# PressureCurrentSource.net
KiCad netlist of a schematic drawn in Altium Designer
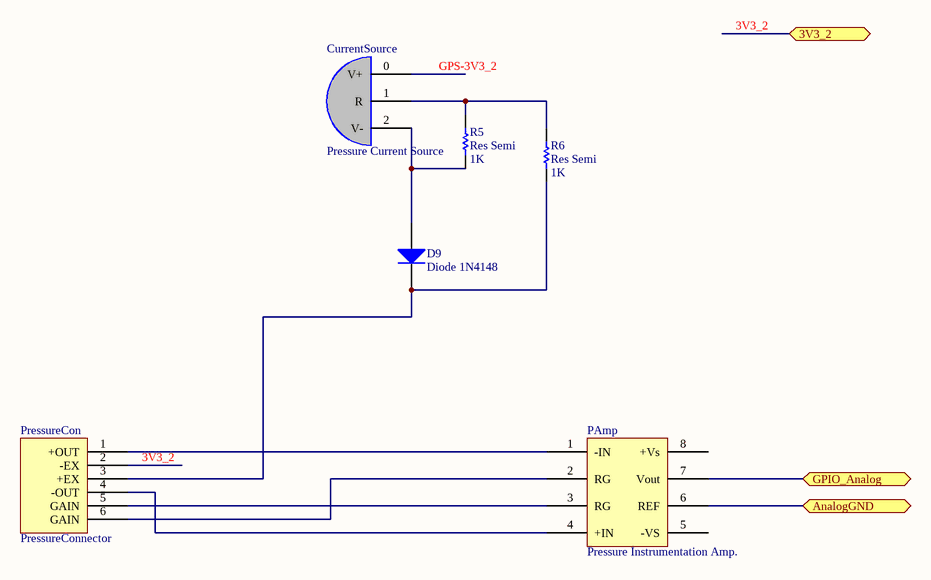
[diagram p0: PressureCurrentSource.SchDoc]

(export (version "E")
  (design (tool "Eeschema 10.0.6"))
  (components
    (comp (ref "CurrentSource")
      (value "Pressure Current Source")
      (footprint "UmbilicalConnectors:Pressure Current Source")
      (libsource (lib "UmbilicalBoardV2") (part "Pressure Current Source"))
    )
    (comp (ref "D9")
      (value "Diode 1N4148")
      (footprint "DO-35")
      (description "High Conductance Fast Diode")
      (fields (field (name "PUBLISHER") "Altium Limited"))
      (libsource (lib "Miscellaneous Devices") (part "Diode 1N4148"))
    )
    (comp (ref "PAmp")
      (value "Pressure Instrumentation Amp.")
      (footprint "UmbilicalConnectors:Pressure Instrumentation Amp.")
      (libsource (lib "UmbilicalBoardV2") (part "Pressure Instrumentation Amp."))
    )
    (comp (ref "PressureCon")
      (value "PressureConnector")
      (footprint "UmbilicalConnectors:Pressure Connector")
      (description "Molex 70553-0005")
      (libsource (lib "UmbilicalBoardV2") (part "PressureConnector"))
    )
    (comp (ref "R5")
      (value "Res Semi")
      (footprint "AXIAL-0.5")
      (description "Semiconductor Resistor")
      (fields (field (name "ALTIUM_VALUE") "1K") (field (name "PUBLISHER") "Altium Limited"))
      (libsource (lib "Miscellaneous Devices") (part "Res Semi"))
    )
    (comp (ref "R6")
      (value "Res Semi")
      (footprint "AXIAL-0.5")
      (description "Semiconductor Resistor")
      (fields (field (name "ALTIUM_VALUE") "1K") (field (name "PUBLISHER") "Altium Limited"))
      (libsource (lib "Miscellaneous Devices") (part "Res Semi"))
    )
  )
  (nets
    (net (code "1") (name "/3V3_2") (class "Default")
      (node (ref "PressureCon") (pin "2") (pinfunction "-EX_2") (pintype "passive"))
    )
    (net (code "2") (name "/AnalogGND") (class "Default")
      (node (ref "PAmp") (pin "6") (pinfunction "REF_6") (pintype "passive"))
    )
    (net (code "3") (name "/GPIO_Analog") (class "Default")
      (node (ref "PAmp") (pin "7") (pinfunction "Vout_7") (pintype "passive"))
    )
    (net (code "4") (name "/GPS-3V3_2") (class "Default")
      (node (ref "CurrentSource") (pin "0") (pinfunction "V+_0") (pintype "passive"))
    )
    (net (code "5") (name "Net-(CurrentSource-R)") (class "Default")
      (node (ref "CurrentSource") (pin "1") (pinfunction "R_1") (pintype "passive"))
      (node (ref "R5") (pin "2") (pinfunction "2_2") (pintype "passive"))
      (node (ref "R6") (pin "2") (pinfunction "2_2") (pintype "passive"))
    )
    (net (code "6") (name "Net-(CurrentSource-V-)") (class "Default")
      (node (ref "CurrentSource") (pin "2") (pinfunction "V-_2") (pintype "passive"))
      (node (ref "D9") (pin "1") (pinfunction "A_1") (pintype "passive"))
      (node (ref "R5") (pin "1") (pinfunction "1_1") (pintype "passive"))
    )
    (net (code "7") (name "Net-(D9-K)") (class "Default")
      (node (ref "D9") (pin "2") (pinfunction "K_2") (pintype "passive"))
      (node (ref "PressureCon") (pin "3") (pinfunction "+EX_3") (pintype "passive"))
      (node (ref "R6") (pin "1") (pinfunction "1_1") (pintype "passive"))
    )
    (net (code "8") (name "Net-(PAmp-+IN)") (class "Default")
      (node (ref "PAmp") (pin "4") (pinfunction "+IN_4") (pintype "passive"))
      (node (ref "PressureCon") (pin "4") (pinfunction "-OUT_4") (pintype "passive"))
    )
    (net (code "9") (name "Net-(PAmp--IN)") (class "Default")
      (node (ref "PAmp") (pin "1") (pinfunction "-IN_1") (pintype "passive"))
      (node (ref "PressureCon") (pin "1") (pinfunction "+OUT_1") (pintype "passive"))
    )
    (net (code "10") (name "Net-(PAmp-RG-Pad2)") (class "Default")
      (node (ref "PAmp") (pin "2") (pinfunction "RG_2") (pintype "passive"))
      (node (ref "PressureCon") (pin "6") (pinfunction "GAIN_6") (pintype "passive"))
    )
    (net (code "11") (name "Net-(PAmp-RG-Pad3)") (class "Default")
      (node (ref "PAmp") (pin "3") (pinfunction "RG_3") (pintype "passive"))
      (node (ref "PressureCon") (pin "5") (pinfunction "GAIN_5") (pintype "passive"))
    )
    (net (code "12") (name "unconnected-(PAmp-+Vs-Pad8)") (class "Default")
      (node (ref "PAmp") (pin "8") (pinfunction "+Vs_8") (pintype "passive"))
    )
    (net (code "13") (name "unconnected-(PAmp--VS-Pad5)") (class "Default")
      (node (ref "PAmp") (pin "5") (pinfunction "-VS_5") (pintype "passive"))
    )
  )
)
